# Micro.net
KiCad netlist of a schematic drawn in Altium Designer
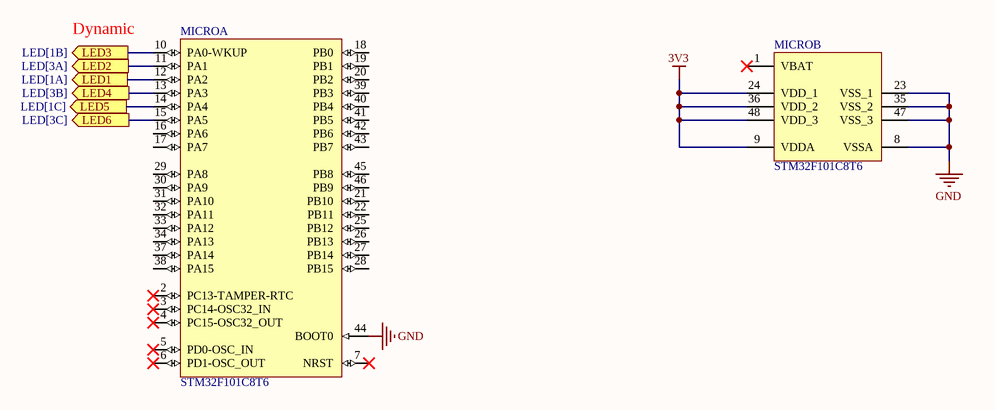
[diagram p0: Micro.SchDoc]

(export (version "E")
  (design (tool "Eeschema 10.0.6"))
  (components
    (comp (ref "MICRO")
      (value "STM32F101C8T6")
      (footprint "STM-LQFP48_N")
      (libsource (lib "STMicroelectronics STM32 F1") (part "STM32F101C8T6"))
    )
  )
  (nets
    (net (code "1") (name "/LED1") (class "Default")
      (node (ref "MICRO") (pin "12") (pinfunction "PA2_12") (pintype "bidirectional"))
    )
    (net (code "2") (name "/LED2") (class "Default")
      (node (ref "MICRO") (pin "11") (pinfunction "PA1_11") (pintype "bidirectional"))
    )
    (net (code "3") (name "/LED3") (class "Default")
      (node (ref "MICRO") (pin "10") (pinfunction "PA0-WKUP_10") (pintype "bidirectional"))
    )
    (net (code "4") (name "/LED4") (class "Default")
      (node (ref "MICRO") (pin "13") (pinfunction "PA3_13") (pintype "bidirectional"))
    )
    (net (code "5") (name "/LED5") (class "Default")
      (node (ref "MICRO") (pin "14") (pinfunction "PA4_14") (pintype "bidirectional"))
    )
    (net (code "6") (name "/LED6") (class "Default")
      (node (ref "MICRO") (pin "15") (pinfunction "PA5_15") (pintype "bidirectional"))
    )
    (net (code "7") (name "3V3") (class "Default")
      (node (ref "MICRO") (pin "24") (pinfunction "VDD_1_24") (pintype "power_in"))
      (node (ref "MICRO") (pin "36") (pinfunction "VDD_2_36") (pintype "power_in"))
      (node (ref "MICRO") (pin "48") (pinfunction "VDD_3_48") (pintype "power_in"))
      (node (ref "MICRO") (pin "9") (pinfunction "VDDA_9") (pintype "power_in"))
    )
    (net (code "8") (name "GND") (class "Default")
      (node (ref "MICRO") (pin "23") (pinfunction "VSS_1_23") (pintype "power_in"))
      (node (ref "MICRO") (pin "35") (pinfunction "VSS_2_35") (pintype "power_in"))
      (node (ref "MICRO") (pin "44") (pinfunction "BOOT0_44") (pintype "input"))
      (node (ref "MICRO") (pin "47") (pinfunction "VSS_3_47") (pintype "power_in"))
      (node (ref "MICRO") (pin "8") (pinfunction "VSSA_8") (pintype "power_in"))
    )
    (net (code "9") (name "unconnected-(MICROA-NRST-Pad7)") (class "Default")
      (node (ref "MICRO") (pin "7") (pinfunction "NRST_7") (pintype "bidirectional+no_connect"))
    )
    (net (code "10") (name "unconnected-(MICROA-PA6-Pad16)") (class "Default")
      (node (ref "MICRO") (pin "16") (pinfunction "PA6_16") (pintype "bidirectional"))
    )
    (net (code "11") (name "unconnected-(MICROA-PA7-Pad17)") (class "Default")
      (node (ref "MICRO") (pin "17") (pinfunction "PA7_17") (pintype "bidirectional"))
    )
    (net (code "12") (name "unconnected-(MICROA-PA8-Pad29)") (class "Default")
      (node (ref "MICRO") (pin "29") (pinfunction "PA8_29") (pintype "bidirectional"))
    )
    (net (code "13") (name "unconnected-(MICROA-PA9-Pad30)") (class "Default")
      (node (ref "MICRO") (pin "30") (pinfunction "PA9_30") (pintype "bidirectional"))
    )
    (net (code "14") (name "unconnected-(MICROA-PA10-Pad31)") (class "Default")
      (node (ref "MICRO") (pin "31") (pinfunction "PA10_31") (pintype "bidirectional"))
    )
    (net (code "15") (name "unconnected-(MICROA-PA11-Pad32)") (class "Default")
      (node (ref "MICRO") (pin "32") (pinfunction "PA11_32") (pintype "bidirectional"))
    )
    (net (code "16") (name "unconnected-(MICROA-PA12-Pad33)") (class "Default")
      (node (ref "MICRO") (pin "33") (pinfunction "PA12_33") (pintype "bidirectional"))
    )
    (net (code "17") (name "unconnected-(MICROA-PA13-Pad34)") (class "Default")
      (node (ref "MICRO") (pin "34") (pinfunction "PA13_34") (pintype "bidirectional"))
    )
    (net (code "18") (name "unconnected-(MICROA-PA14-Pad37)") (class "Default")
      (node (ref "MICRO") (pin "37") (pinfunction "PA14_37") (pintype "bidirectional"))
    )
    (net (code "19") (name "unconnected-(MICROA-PA15-Pad38)") (class "Default")
      (node (ref "MICRO") (pin "38") (pinfunction "PA15_38") (pintype "bidirectional"))
    )
    (net (code "20") (name "unconnected-(MICROA-PB0-Pad18)") (class "Default")
      (node (ref "MICRO") (pin "18") (pinfunction "PB0_18") (pintype "bidirectional"))
    )
    (net (code "21") (name "unconnected-(MICROA-PB1-Pad19)") (class "Default")
      (node (ref "MICRO") (pin "19") (pinfunction "PB1_19") (pintype "bidirectional"))
    )
    (net (code "22") (name "unconnected-(MICROA-PB2-Pad20)") (class "Default")
      (node (ref "MICRO") (pin "20") (pinfunction "PB2_20") (pintype "bidirectional"))
    )
    (net (code "23") (name "unconnected-(MICROA-PB3-Pad39)") (class "Default")
      (node (ref "MICRO") (pin "39") (pinfunction "PB3_39") (pintype "bidirectional"))
    )
    (net (code "24") (name "unconnected-(MICROA-PB4-Pad40)") (class "Default")
      (node (ref "MICRO") (pin "40") (pinfunction "PB4_40") (pintype "bidirectional"))
    )
    (net (code "25") (name "unconnected-(MICROA-PB5-Pad41)") (class "Default")
      (node (ref "MICRO") (pin "41") (pinfunction "PB5_41") (pintype "bidirectional"))
    )
    (net (code "26") (name "unconnected-(MICROA-PB6-Pad42)") (class "Default")
      (node (ref "MICRO") (pin "42") (pinfunction "PB6_42") (pintype "bidirectional"))
    )
    (net (code "27") (name "unconnected-(MICROA-PB7-Pad43)") (class "Default")
      (node (ref "MICRO") (pin "43") (pinfunction "PB7_43") (pintype "bidirectional"))
    )
    (net (code "28") (name "unconnected-(MICROA-PB8-Pad45)") (class "Default")
      (node (ref "MICRO") (pin "45") (pinfunction "PB8_45") (pintype "bidirectional"))
    )
    (net (code "29") (name "unconnected-(MICROA-PB9-Pad46)") (class "Default")
      (node (ref "MICRO") (pin "46") (pinfunction "PB9_46") (pintype "bidirectional"))
    )
    (net (code "30") (name "unconnected-(MICROA-PB10-Pad21)") (class "Default")
      (node (ref "MICRO") (pin "21") (pinfunction "PB10_21") (pintype "bidirectional"))
    )
    (net (code "31") (name "unconnected-(MICROA-PB11-Pad22)") (class "Default")
      (node (ref "MICRO") (pin "22") (pinfunction "PB11_22") (pintype "bidirectional"))
    )
    (net (code "32") (name "unconnected-(MICROA-PB12-Pad25)") (class "Default")
      (node (ref "MICRO") (pin "25") (pinfunction "PB12_25") (pintype "bidirectional"))
    )
    (net (code "33") (name "unconnected-(MICROA-PB13-Pad26)") (class "Default")
      (node (ref "MICRO") (pin "26") (pinfunction "PB13_26") (pintype "bidirectional"))
    )
    (net (code "34") (name "unconnected-(MICROA-PB14-Pad27)") (class "Default")
      (node (ref "MICRO") (pin "27") (pinfunction "PB14_27") (pintype "bidirectional"))
    )
    (net (code "35") (name "unconnected-(MICROA-PB15-Pad28)") (class "Default")
      (node (ref "MICRO") (pin "28") (pinfunction "PB15_28") (pintype "bidirectional"))
    )
    (net (code "36") (name "unconnected-(MICROA-PC13-TAMPER-RTC-Pad2)") (class "Default")
      (node (ref "MICRO") (pin "2") (pinfunction "PC13-TAMPER-RTC_2") (pintype "bidirectional+no_connect"))
    )
    (net (code "37") (name "unconnected-(MICROA-PC14-OSC32_IN-Pad3)") (class "Default")
      (node (ref "MICRO") (pin "3") (pinfunction "PC14-OSC32_IN_3") (pintype "bidirectional+no_connect"))
    )
    (net (code "38") (name "unconnected-(MICROA-PC15-OSC32_OUT-Pad4)") (class "Default")
      (node (ref "MICRO") (pin "4") (pinfunction "PC15-OSC32_OUT_4") (pintype "bidirectional+no_connect"))
    )
    (net (code "39") (name "unconnected-(MICROA-PD0-OSC_IN-Pad5)") (class "Default")
      (node (ref "MICRO") (pin "5") (pinfunction "PD0-OSC_IN_5") (pintype "bidirectional+no_connect"))
    )
    (net (code "40") (name "unconnected-(MICROA-PD1-OSC_OUT-Pad6)") (class "Default")
      (node (ref "MICRO") (pin "6") (pinfunction "PD1-OSC_OUT_6") (pintype "bidirectional+no_connect"))
    )
    (net (code "41") (name "unconnected-(MICROB-VBAT-Pad1)") (class "Default")
      (node (ref "MICRO") (pin "1") (pinfunction "VBAT_1") (pintype "power_in+no_connect"))
    )
  )
)
